# Sheet1.net
KiCad netlist of a schematic drawn in Altium Designer
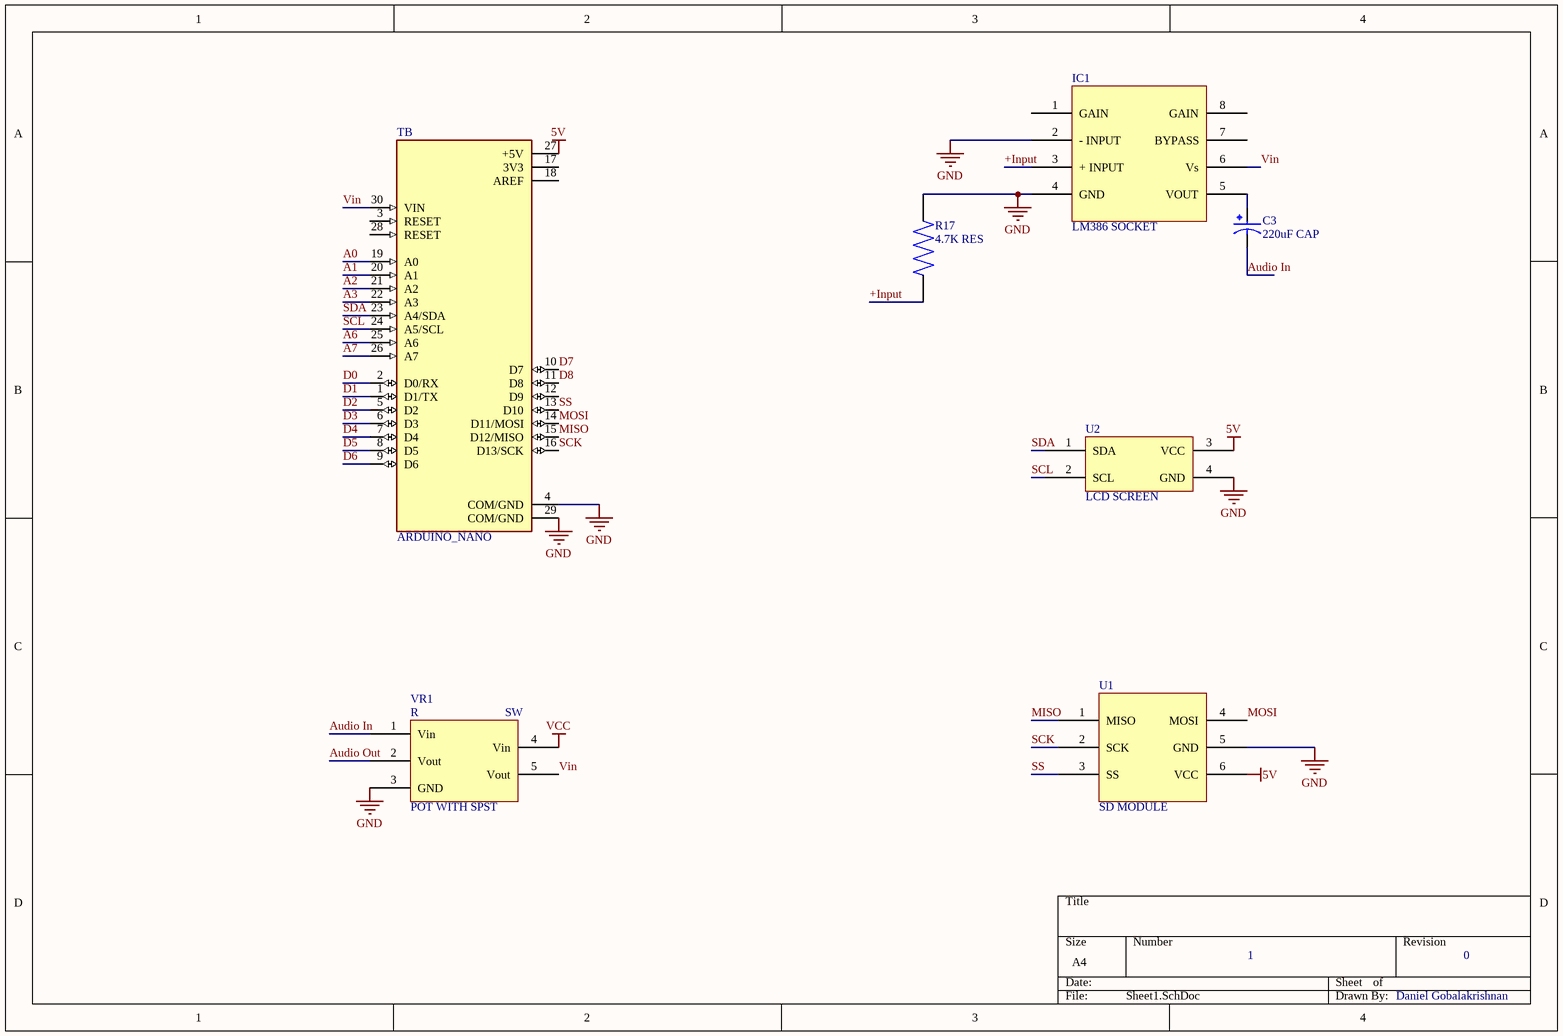
[diagram p0: Sheet1.SchDoc]

(export (version "E")
  (design (tool "Eeschema 10.0.6"))
  (components
    (comp (ref "C3")
      (value "220uF CAP")
      (footprint "220uF CAP")
      (description "33ÂµF 250V Aluminum Electrolytic Capacitors Radial, Can 5000 Hrs @ 105Â°C")
      (fields (field (name "MP") "UPM2E330MHD1TN") (field (name "MF") "Nichicon"))
      (libsource (lib "Library") (part "220uF CAP"))
    )
    (comp (ref "IC1")
      (value "LM386 SOCKET")
      (footprint "LM386 SOCKET")
      (description "8 pin IC socket for LM386")
      (libsource (lib "Library") (part "LM386 SOCKET"))
    )
    (comp (ref "R17")
      (value "4.7K RES")
      (footprint "4.7K RES")
      (fields (field (name "MP") "RMCF1206FT4K70"))
      (libsource (lib "Library") (part "4.7K RES"))
    )
    (comp (ref "TB")
      (value "ARDUINO_NANO")
      (footprint "SHIELD_ARDUINO_NANO")
      (description "ATSAMD21G18A Arduino Nano 33 IoT SAM D ARMÂ® CortexÂ®-M0+ MCU 32-Bit Embedded Evaluation Board")
      (fields (field (name "MP") "ARDUINO NANO") (field (name "MF") "Arduino"))
      (libsource (lib "Library") (part "ARDUINO_NANO"))
    )
    (comp (ref "U1")
      (value "SD MODULE")
      (footprint "SD MODULE")
      (libsource (lib "Library") (part "SD MODULE"))
    )
    (comp (ref "U2")
      (value "LCD SCREEN")
      (footprint "LCD SCREEN")
      (libsource (lib "Library") (part "LCD SCREEN"))
    )
    (comp (ref "VR1")
      (value "POT WITH SPST")
      (footprint "POT WITH SPST")
      (description "Potentiometer with SPST Switch")
      (libsource (lib "Library") (part "POT WITH SPST"))
    )
  )
  (nets
    (net (code "1") (name "/+Input") (class "Default")
      (node (ref "IC1") (pin "3") (pinfunction "+_INPUT_3") (pintype "passive"))
      (node (ref "R17") (pin "1") (pinfunction "1_1") (pintype "passive"))
    )
    (net (code "2") (name "/A0") (class "Default")
      (node (ref "TB") (pin "19") (pinfunction "A0_19") (pintype "input"))
    )
    (net (code "3") (name "/A1") (class "Default")
      (node (ref "TB") (pin "20") (pinfunction "A1_20") (pintype "input"))
    )
    (net (code "4") (name "/A2") (class "Default")
      (node (ref "TB") (pin "21") (pinfunction "A2_21") (pintype "input"))
    )
    (net (code "5") (name "/A3") (class "Default")
      (node (ref "TB") (pin "22") (pinfunction "A3_22") (pintype "input"))
    )
    (net (code "6") (name "/A6") (class "Default")
      (node (ref "TB") (pin "25") (pinfunction "A6_25") (pintype "input"))
    )
    (net (code "7") (name "/A7") (class "Default")
      (node (ref "TB") (pin "26") (pinfunction "A7_26") (pintype "input"))
    )
    (net (code "8") (name "/Audio In") (class "Default")
      (node (ref "C3") (pin "N") (pinfunction "N_N") (pintype "passive"))
      (node (ref "VR1") (pin "1") (pinfunction "Vin_1") (pintype "passive"))
    )
    (net (code "9") (name "/Audio Out") (class "Default")
      (node (ref "VR1") (pin "2") (pinfunction "Vout_2") (pintype "passive"))
    )
    (net (code "10") (name "/D0") (class "Default")
      (node (ref "TB") (pin "2") (pinfunction "D0/RX_2") (pintype "bidirectional"))
    )
    (net (code "11") (name "/D1") (class "Default")
      (node (ref "TB") (pin "1") (pinfunction "D1/TX_1") (pintype "bidirectional"))
    )
    (net (code "12") (name "/D2") (class "Default")
      (node (ref "TB") (pin "5") (pinfunction "D2_5") (pintype "bidirectional"))
    )
    (net (code "13") (name "/D3") (class "Default")
      (node (ref "TB") (pin "6") (pinfunction "D3_6") (pintype "bidirectional"))
    )
    (net (code "14") (name "/D4") (class "Default")
      (node (ref "TB") (pin "7") (pinfunction "D4_7") (pintype "bidirectional"))
    )
    (net (code "15") (name "/D5") (class "Default")
      (node (ref "TB") (pin "8") (pinfunction "D5_8") (pintype "bidirectional"))
    )
    (net (code "16") (name "/D6") (class "Default")
      (node (ref "TB") (pin "9") (pinfunction "D6_9") (pintype "bidirectional"))
    )
    (net (code "17") (name "/D7") (class "Default")
      (node (ref "TB") (pin "10") (pinfunction "D7_10") (pintype "bidirectional"))
    )
    (net (code "18") (name "/D8") (class "Default")
      (node (ref "TB") (pin "11") (pinfunction "D8_11") (pintype "bidirectional"))
    )
    (net (code "19") (name "/MISO") (class "Default")
      (node (ref "TB") (pin "15") (pinfunction "D12/MISO_15") (pintype "bidirectional"))
      (node (ref "U1") (pin "1") (pinfunction "MISO_1") (pintype "passive"))
    )
    (net (code "20") (name "/MOSI") (class "Default")
      (node (ref "TB") (pin "14") (pinfunction "D11/MOSI_14") (pintype "bidirectional"))
      (node (ref "U1") (pin "4") (pinfunction "MOSI_4") (pintype "passive"))
    )
    (net (code "21") (name "/SCK") (class "Default")
      (node (ref "TB") (pin "16") (pinfunction "D13/SCK_16") (pintype "bidirectional"))
      (node (ref "U1") (pin "2") (pinfunction "SCK_2") (pintype "passive"))
    )
    (net (code "22") (name "/SCL") (class "Default")
      (node (ref "TB") (pin "24") (pinfunction "A5/SCL_24") (pintype "input"))
      (node (ref "U2") (pin "2") (pinfunction "SCL_2") (pintype "passive"))
    )
    (net (code "23") (name "/SDA") (class "Default")
      (node (ref "TB") (pin "23") (pinfunction "A4/SDA_23") (pintype "input"))
      (node (ref "U2") (pin "1") (pinfunction "SDA_1") (pintype "passive"))
    )
    (net (code "24") (name "/SS") (class "Default")
      (node (ref "TB") (pin "13") (pinfunction "D10_13") (pintype "bidirectional"))
      (node (ref "U1") (pin "3") (pinfunction "SS_3") (pintype "passive"))
    )
    (net (code "25") (name "/Vin") (class "Default")
      (node (ref "IC1") (pin "6") (pinfunction "Vs_6") (pintype "passive"))
      (node (ref "TB") (pin "30") (pinfunction "VIN_30") (pintype "input"))
      (node (ref "VR1") (pin "5") (pinfunction "Vout_5") (pintype "passive"))
    )
    (net (code "26") (name "5V") (class "Default")
      (node (ref "TB") (pin "27") (pinfunction "+5V_27") (pintype "power_in"))
      (node (ref "U1") (pin "6") (pinfunction "VCC_6") (pintype "passive"))
      (node (ref "U2") (pin "3") (pinfunction "VCC_3") (pintype "passive"))
    )
    (net (code "27") (name "GND") (class "Default")
      (node (ref "IC1") (pin "2") (pinfunction "-_INPUT_2") (pintype "passive"))
      (node (ref "IC1") (pin "4") (pinfunction "GND_4") (pintype "passive"))
      (node (ref "R17") (pin "2") (pinfunction "2_2") (pintype "passive"))
      (node (ref "TB") (pin "29") (pinfunction "COM/GND_29") (pintype "power_in"))
      (node (ref "TB") (pin "4") (pinfunction "COM/GND_4") (pintype "power_in"))
      (node (ref "U1") (pin "5") (pinfunction "GND_5") (pintype "passive"))
      (node (ref "U2") (pin "4") (pinfunction "GND_4") (pintype "passive"))
      (node (ref "VR1") (pin "3") (pinfunction "GND_3") (pintype "passive"))
    )
    (net (code "28") (name "Net-(IC1-VOUT)") (class "Default")
      (node (ref "C3") (pin "P") (pinfunction "P_P") (pintype "passive"))
      (node (ref "IC1") (pin "5") (pinfunction "VOUT_5") (pintype "passive"))
    )
    (net (code "29") (name "VCC") (class "Default")
      (node (ref "VR1") (pin "4") (pinfunction "Vin_4") (pintype "passive"))
    )
    (net (code "30") (name "unconnected-(IC1-BYPASS-Pad7)") (class "Default")
      (node (ref "IC1") (pin "7") (pinfunction "BYPASS_7") (pintype "passive"))
    )
    (net (code "31") (name "unconnected-(IC1-GAIN-Pad1)") (class "Default")
      (node (ref "IC1") (pin "1") (pinfunction "GAIN_1") (pintype "passive"))
    )
    (net (code "32") (name "unconnected-(IC1-GAIN-Pad8)") (class "Default")
      (node (ref "IC1") (pin "8") (pinfunction "GAIN_8") (pintype "passive"))
    )
    (net (code "33") (name "unconnected-(TB-3V3-Pad17)") (class "Default")
      (node (ref "TB") (pin "17") (pinfunction "3V3_17") (pintype "power_in"))
    )
    (net (code "34") (name "unconnected-(TB-AREF-Pad18)") (class "Default")
      (node (ref "TB") (pin "18") (pinfunction "AREF_18") (pintype "power_in"))
    )
    (net (code "35") (name "unconnected-(TB-D9-Pad12)") (class "Default")
      (node (ref "TB") (pin "12") (pinfunction "D9_12") (pintype "bidirectional"))
    )
    (net (code "36") (name "unconnected-(TB-RESET-Pad3)") (class "Default")
      (node (ref "TB") (pin "3") (pinfunction "RESET_3") (pintype "input"))
    )
    (net (code "37") (name "unconnected-(TB-RESET-Pad28)") (class "Default")
      (node (ref "TB") (pin "28") (pinfunction "RESET_28") (pintype "input"))
    )
  )
)
